# SCH_Aether_Zero_R0_2.net
KiCad netlist of a schematic drawn in EasyEDA
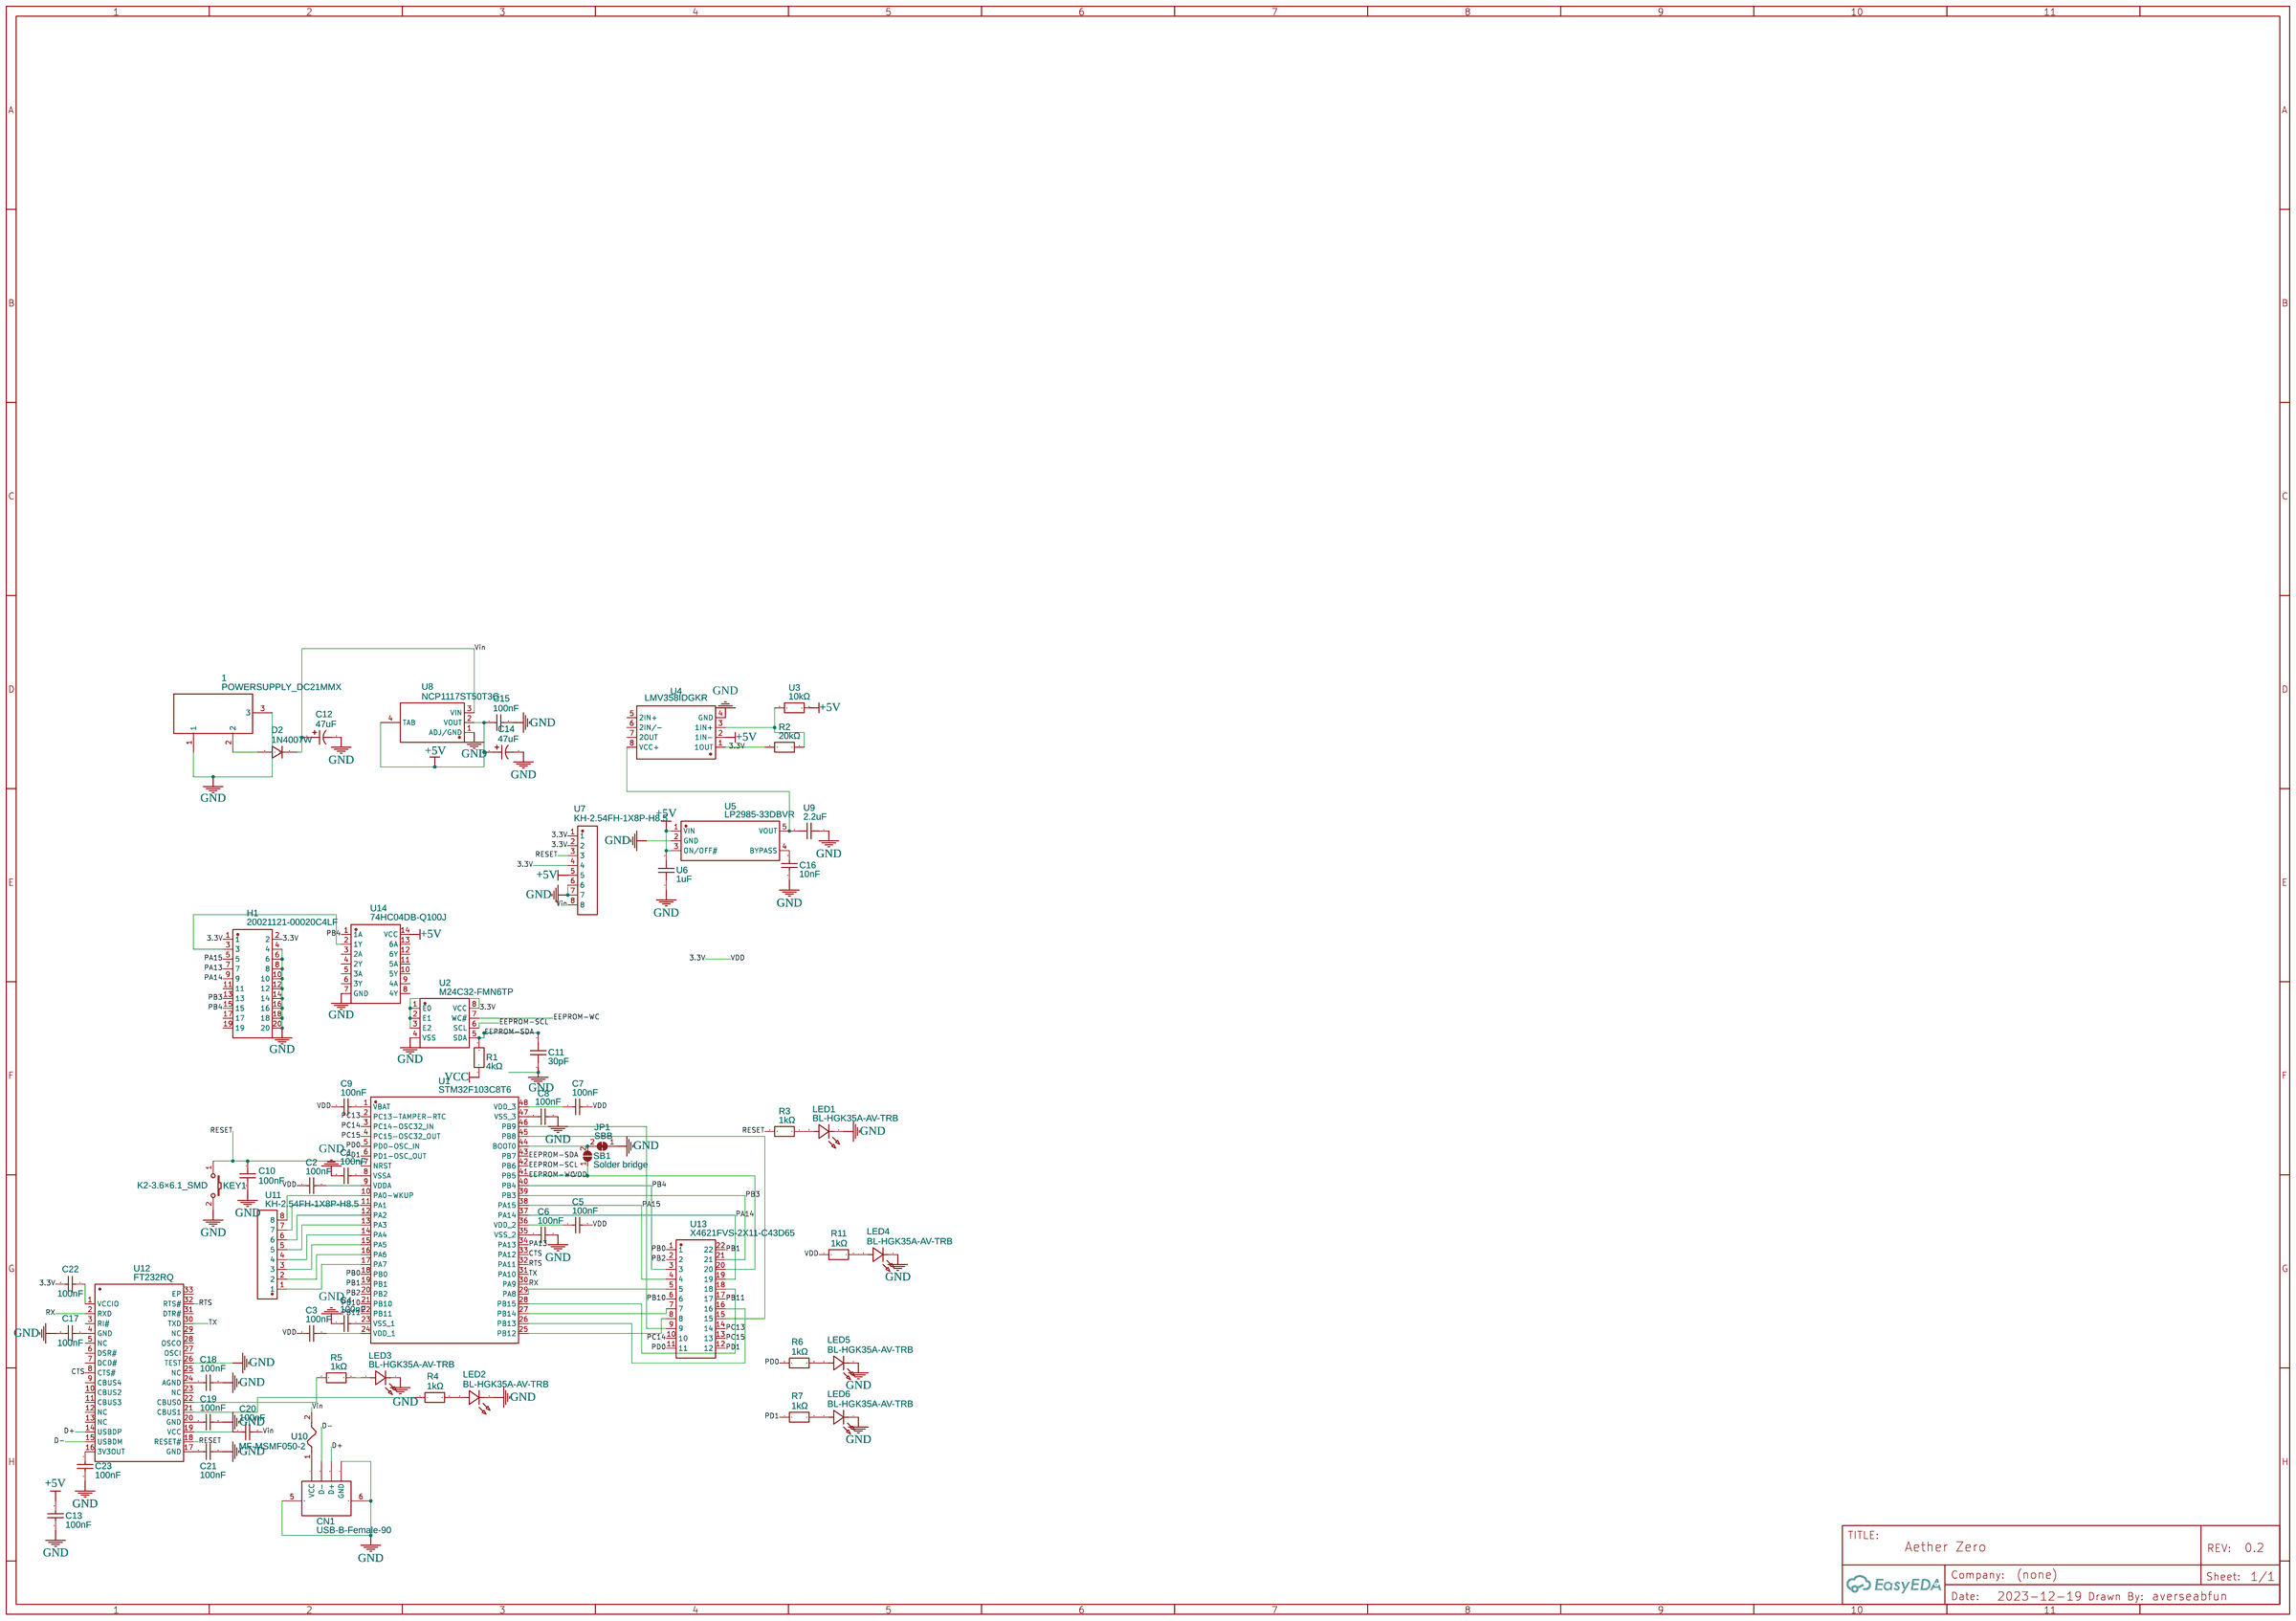
[diagram p0: schematic sheet]

(export (version "E")
  (design (tool "Eeschema 10.0.6"))
  (components
    (comp (ref "1") (value "POWERSUPPLY_DC21MMX") (libsource (lib "") (part "POWERSUPPLY_DC21MMX")))
    (comp (ref "C1")
      (value "100nF")
      (fields (field (name "Manufacturer Part") "0402B104K160NT") (field (name "Manufacturer") "FH(风华)"))
      (libsource (lib "") (part "0402B104K160NT"))
    )
    (comp (ref "C2")
      (value "100nF")
      (fields (field (name "Manufacturer Part") "0402B104K160NT") (field (name "Manufacturer") "FH(风华)"))
      (libsource (lib "") (part "0402B104K160NT"))
    )
    (comp (ref "C3")
      (value "100nF")
      (fields (field (name "Manufacturer Part") "0402B104K160NT") (field (name "Manufacturer") "FH(风华)"))
      (libsource (lib "") (part "0402B104K160NT"))
    )
    (comp (ref "C4")
      (value "100nF")
      (fields (field (name "Manufacturer Part") "0402B104K160NT") (field (name "Manufacturer") "FH(风华)"))
      (libsource (lib "") (part "0402B104K160NT"))
    )
    (comp (ref "C5")
      (value "100nF")
      (fields (field (name "Manufacturer Part") "0402B104K160NT") (field (name "Manufacturer") "FH(风华)"))
      (libsource (lib "") (part "0402B104K160NT_2"))
    )
    (comp (ref "C6")
      (value "100nF")
      (fields (field (name "Manufacturer Part") "0402B104K160NT") (field (name "Manufacturer") "FH(风华)"))
      (libsource (lib "") (part "0402B104K160NT_2"))
    )
    (comp (ref "C7")
      (value "100nF")
      (fields (field (name "Manufacturer Part") "0402B104K160NT") (field (name "Manufacturer") "FH(风华)"))
      (libsource (lib "") (part "0402B104K160NT_2"))
    )
    (comp (ref "C8")
      (value "100nF")
      (fields (field (name "Manufacturer Part") "0402B104K160NT") (field (name "Manufacturer") "FH(风华)"))
      (libsource (lib "") (part "0402B104K160NT_2"))
    )
    (comp (ref "C9")
      (value "100nF")
      (fields (field (name "Manufacturer Part") "0402B104K160NT") (field (name "Manufacturer") "FH(风华)"))
      (libsource (lib "") (part "0402B104K160NT"))
    )
    (comp (ref "C10")
      (value "100nF")
      (fields (field (name "Manufacturer Part") "0402B104K160NT") (field (name "Manufacturer") "FH(风华)"))
      (libsource (lib "") (part "0402B104K160NT_1"))
    )
    (comp (ref "C11")
      (value "30pF")
      (fields
        (field (name "Manufacturer Part") "AC0402JRNPO9BN300")
        (field (name "Manufacturer") "YAGEO(国巨)")
      )
      (libsource (lib "") (part "AC0402JRNPO9BN300"))
    )
    (comp (ref "C12")
      (value "47uF")
      (fields
        (field (name "Manufacturer Part") "RVT47UF35V67RV0039")
        (field (name "Manufacturer") "KNSCHA(科尼盛)")
      )
      (libsource (lib "") (part "RVT47UF35V67RV0039"))
    )
    (comp (ref "C13")
      (value "100nF")
      (fields (field (name "Manufacturer Part") "0402B104K160NT") (field (name "Manufacturer") "FH(风华)"))
      (libsource (lib "") (part "0402B104K160NT_3"))
    )
    (comp (ref "C14")
      (value "47uF")
      (fields
        (field (name "Manufacturer Part") "RVT47UF35V67RV0039")
        (field (name "Manufacturer") "KNSCHA(科尼盛)")
      )
      (libsource (lib "") (part "RVT47UF35V67RV0039"))
    )
    (comp (ref "C15")
      (value "100nF")
      (fields (field (name "Manufacturer Part") "0402B104K160NT") (field (name "Manufacturer") "FH(风华)"))
      (libsource (lib "") (part "0402B104K160NT_2"))
    )
    (comp (ref "C16")
      (value "10nF")
      (fields (field (name "Manufacturer Part") "0402B103K500NT") (field (name "Manufacturer") "FH(风华)"))
      (libsource (lib "") (part "0402B103K500NT"))
    )
    (comp (ref "C17")
      (value "100nF")
      (fields (field (name "Manufacturer Part") "0402B104K160NT") (field (name "Manufacturer") "FH(风华)"))
      (libsource (lib "") (part "0402B104K160NT"))
    )
    (comp (ref "C18")
      (value "100nF")
      (fields (field (name "Manufacturer Part") "0402B104K160NT") (field (name "Manufacturer") "FH(风华)"))
      (libsource (lib "") (part "0402B104K160NT_2"))
    )
    (comp (ref "C19")
      (value "100nF")
      (fields (field (name "Manufacturer Part") "0402B104K160NT") (field (name "Manufacturer") "FH(风华)"))
      (libsource (lib "") (part "0402B104K160NT_2"))
    )
    (comp (ref "C20")
      (value "100nF")
      (fields (field (name "Manufacturer Part") "0402B104K160NT") (field (name "Manufacturer") "FH(风华)"))
      (libsource (lib "") (part "0402B104K160NT_2"))
    )
    (comp (ref "C21")
      (value "100nF")
      (fields (field (name "Manufacturer Part") "0402B104K160NT") (field (name "Manufacturer") "FH(风华)"))
      (libsource (lib "") (part "0402B104K160NT_2"))
    )
    (comp (ref "C22")
      (value "100nF")
      (fields (field (name "Manufacturer Part") "0402B104K160NT") (field (name "Manufacturer") "FH(风华)"))
      (libsource (lib "") (part "0402B104K160NT"))
    )
    (comp (ref "C23")
      (value "100nF")
      (fields (field (name "Manufacturer Part") "0402B104K160NT") (field (name "Manufacturer") "FH(风华)"))
      (libsource (lib "") (part "0402B104K160NT_1"))
    )
    (comp (ref "CN1")
      (value "USB-B-Female-90")
      (fields (field (name "Manufacturer Part") "921-111A1010D10200") (field (name "Manufacturer") "精拓金"))
      (libsource (lib "") (part "USB-B-Female-90"))
    )
    (comp (ref "D2")
      (value "1N4007W")
      (fields (field (name "Manufacturer") "BLUE ROCKET"))
      (libsource (lib "") (part "1N4007W"))
    )
    (comp (ref "H1")
      (value "20021121-00020C4LF")
      (fields (field (name "Manufacturer") "Amphenol"))
      (libsource (lib "") (part "20021121-00020C4LF"))
    )
    (comp (ref "JP1") (value "SBB") (libsource (lib "") (part "SBB")))
    (comp (ref "KEY1")
      (value "K2-3.6×6.1_SMD")
      (fields (field (name "Manufacturer Part") "K2-1107ST-A4SW-06"))
      (libsource (lib "") (part "K2-3.6×6.1_SMD"))
    )
    (comp (ref "LED1")
      (value "BL-HGK35A-AV-TRB")
      (fields (field (name "Manufacturer") "BrtLed(佰鸿)"))
      (libsource (lib "") (part "BL-HGK35A-AV-TRB"))
    )
    (comp (ref "LED2")
      (value "BL-HGK35A-AV-TRB")
      (fields (field (name "Manufacturer") "BrtLed(佰鸿)"))
      (libsource (lib "") (part "BL-HGK35A-AV-TRB"))
    )
    (comp (ref "LED3")
      (value "BL-HGK35A-AV-TRB")
      (fields (field (name "Manufacturer") "BrtLed(佰鸿)"))
      (libsource (lib "") (part "BL-HGK35A-AV-TRB"))
    )
    (comp (ref "LED4")
      (value "BL-HGK35A-AV-TRB")
      (fields (field (name "Manufacturer") "BrtLed(佰鸿)"))
      (libsource (lib "") (part "BL-HGK35A-AV-TRB"))
    )
    (comp (ref "LED5")
      (value "BL-HGK35A-AV-TRB")
      (fields (field (name "Manufacturer") "BrtLed(佰鸿)"))
      (libsource (lib "") (part "BL-HGK35A-AV-TRB"))
    )
    (comp (ref "LED6")
      (value "BL-HGK35A-AV-TRB")
      (fields (field (name "Manufacturer") "BrtLed(佰鸿)"))
      (libsource (lib "") (part "BL-HGK35A-AV-TRB"))
    )
    (comp (ref "R1")
      (value "4kΩ")
      (fields (field (name "Manufacturer Part") "RN732BTTD4001B25") (field (name "Manufacturer") "KOA"))
      (libsource (lib "") (part "RN732BTTD4001B25"))
    )
    (comp (ref "R2")
      (value "20kΩ")
      (fields (field (name "Manufacturer Part") "RT0402BRD0720KL") (field (name "Manufacturer") "YAGEO(国巨)"))
      (libsource (lib "") (part "RT0402BRD0720KL"))
    )
    (comp (ref "R3")
      (value "1kΩ")
      (fields (field (name "Manufacturer Part") "CR-03JA7----1K") (field (name "Manufacturer") "Viking Tech"))
      (libsource (lib "") (part "CR-03JA7----1K"))
    )
    (comp (ref "R4")
      (value "1kΩ")
      (fields (field (name "Manufacturer Part") "CR-03JA7----1K") (field (name "Manufacturer") "Viking Tech"))
      (libsource (lib "") (part "CR-03JA7----1K_1"))
    )
    (comp (ref "R5")
      (value "1kΩ")
      (fields (field (name "Manufacturer Part") "CR-03JA7----1K") (field (name "Manufacturer") "Viking Tech"))
      (libsource (lib "") (part "CR-03JA7----1K"))
    )
    (comp (ref "R6")
      (value "1kΩ")
      (fields (field (name "Manufacturer Part") "CR-03JA7----1K") (field (name "Manufacturer") "Viking Tech"))
      (libsource (lib "") (part "CR-03JA7----1K_1"))
    )
    (comp (ref "R7")
      (value "1kΩ")
      (fields (field (name "Manufacturer Part") "CR-03JA7----1K") (field (name "Manufacturer") "Viking Tech"))
      (libsource (lib "") (part "CR-03JA7----1K_1"))
    )
    (comp (ref "R11")
      (value "1kΩ")
      (fields (field (name "Manufacturer Part") "CR-03JA7----1K") (field (name "Manufacturer") "Viking Tech"))
      (libsource (lib "") (part "CR-03JA7----1K_1"))
    )
    (comp (ref "SB1")
      (value "Solder bridge")
      (fields (field (name "Manufacturer Part") "DNP"))
      (libsource (lib "") (part "Solder bridge"))
    )
    (comp (ref "U1")
      (value "STM32F103C8T6")
      (fields (field (name "Manufacturer") "ST(意法半导体)"))
      (libsource (lib "") (part "STM32F103C8T6"))
    )
    (comp (ref "U2")
      (value "M24C32-FMN6TP")
      (fields (field (name "Manufacturer") "ST(意法半导体)"))
      (libsource (lib "") (part "M24C32-FMN6TP"))
    )
    (comp (ref "U3")
      (value "10kΩ")
      (fields
        (field (name "Manufacturer Part") "TC0625B1002T5J")
        (field (name "Manufacturer") "UNI-ROYAL(厚声)")
      )
      (libsource (lib "") (part "TC0625B1002T5J"))
    )
    (comp (ref "U4")
      (value "LMV358IDGKR")
      (fields (field (name "Manufacturer") "TI(德州仪器)"))
      (libsource (lib "") (part "LMV358IDGKR"))
    )
    (comp (ref "U5")
      (value "LP2985-33DBVR")
      (fields (field (name "Manufacturer") "TI(德州仪器)"))
      (libsource (lib "") (part "LP2985-33DBVR"))
    )
    (comp (ref "U6")
      (value "1uF")
      (fields (field (name "Manufacturer Part") "CGA5L3X8R1H105KT0Y0N") (field (name "Manufacturer") "TDK"))
      (libsource (lib "") (part "CGA5L3X8R1H105KT0Y0N"))
    )
    (comp (ref "U7")
      (value "KH-2.54FH-1X8P-H8.5")
      (fields (field (name "Manufacturer") "kinghelm(金航标)"))
      (libsource (lib "") (part "KH-2.54FH-1X8P-H8.5_1"))
    )
    (comp (ref "U8")
      (value "NCP1117ST50T3G")
      (fields (field (name "Manufacturer") "onsemi(安森美)"))
      (libsource (lib "") (part "NCP1117ST50T3G"))
    )
    (comp (ref "U9")
      (value "2.2uF")
      (fields (field (name "Manufacturer Part") "0805X225K250CT") (field (name "Manufacturer") "Walsin(华新科)"))
      (libsource (lib "") (part "0805X225K250CT_C5122273"))
    )
    (comp (ref "U10")
      (value "MF-MSMF050-2")
      (fields (field (name "Manufacturer") "BOURNS"))
      (libsource (lib "") (part "MF-MSMF050-2"))
    )
    (comp (ref "U11")
      (value "KH-2.54FH-1X8P-H8.5")
      (fields (field (name "Manufacturer") "kinghelm(金航标)"))
      (libsource (lib "") (part "KH-2.54FH-1X8P-H8.5"))
    )
    (comp (ref "U12")
      (value "FT232RQ")
      (fields (field (name "Manufacturer Part") "FT232RQ-REEL") (field (name "Manufacturer") "FTDI(飞特帝亚)"))
      (libsource (lib "") (part "FT232RQ"))
    )
    (comp (ref "U13")
      (value "X4621FVS-2X11-C43D65")
      (fields
        (field (name "Manufacturer Part") "X4621FVS-2x11-C43D65")
        (field (name "Manufacturer") "XKB Connectivity(中国星坤)")
      )
      (libsource (lib "") (part "X4621FVS-2X11-C43D65"))
    )
    (comp (ref "U14")
      (value "74HC04DB-Q100J")
      (fields (field (name "Manufacturer") "Nexperia(安世)"))
      (libsource (lib "") (part "74HC04DB-Q100J"))
    )
  )
  (nets
    (net (code "1") (name "+5V") (class "Default")
      (node (ref "C13") (pin "2") (pinfunction "2_2") (pintype "input"))
      (node (ref "C14") (pin "1") (pinfunction "1_1") (pintype "input"))
      (node (ref "C15") (pin "1") (pinfunction "1_1") (pintype "input"))
      (node (ref "U14") (pin "14") (pinfunction "VCC_14") (pintype "unspecified"))
      (node (ref "U3") (pin "2") (pinfunction "2_2") (pintype "unspecified"))
      (node (ref "U4") (pin "2") (pinfunction "1IN-_2") (pintype "unspecified"))
      (node (ref "U5") (pin "1") (pinfunction "VIN_1") (pintype "unspecified"))
      (node (ref "U5") (pin "3") (pinfunction "ON/OFF#_3") (pintype "unspecified"))
      (node (ref "U6") (pin "2") (pinfunction "2_2") (pintype "unspecified"))
      (node (ref "U7") (pin "5") (pinfunction "5_5") (pintype "unspecified"))
      (node (ref "U8") (pin "2") (pinfunction "VOUT_2") (pintype "unspecified"))
      (node (ref "U8") (pin "4") (pinfunction "TAB_4") (pintype "unspecified"))
    )
    (net (code "2") (name "/3.3V") (class "Default")
      (node (ref "C2") (pin "2") (pinfunction "2_2") (pintype "input"))
      (node (ref "C22") (pin "2") (pinfunction "2_2") (pintype "input"))
      (node (ref "C3") (pin "2") (pinfunction "2_2") (pintype "input"))
      (node (ref "C5") (pin "2") (pinfunction "2_2") (pintype "input"))
      (node (ref "C7") (pin "2") (pinfunction "2_2") (pintype "input"))
      (node (ref "C9") (pin "2") (pinfunction "2_2") (pintype "input"))
      (node (ref "H1") (pin "1") (pinfunction "1_1") (pintype "unspecified"))
      (node (ref "H1") (pin "2") (pinfunction "2_2") (pintype "unspecified"))
      (node (ref "R11") (pin "1") (pinfunction "1_1") (pintype "unspecified"))
      (node (ref "R2") (pin "1") (pinfunction "1_1") (pintype "unspecified"))
      (node (ref "SB1") (pin "1") (pinfunction "A_1") (pintype "unspecified"))
      (node (ref "U1") (pin "41") (pinfunction "PB5_41") (pintype "unspecified"))
      (node (ref "U13") (pin "20") (pinfunction "20_20") (pintype "unspecified"))
      (node (ref "U2") (pin "1") (pinfunction "E0_1") (pintype "unspecified"))
      (node (ref "U2") (pin "2") (pinfunction "E1_2") (pintype "unspecified"))
      (node (ref "U2") (pin "3") (pinfunction "E2_3") (pintype "unspecified"))
      (node (ref "U2") (pin "7") (pinfunction "WC#_7") (pintype "unspecified"))
      (node (ref "U2") (pin "8") (pinfunction "VCC_8") (pintype "unspecified"))
      (node (ref "U4") (pin "1") (pinfunction "1OUT_1") (pintype "unspecified"))
      (node (ref "U7") (pin "1") (pinfunction "1_1") (pintype "unspecified"))
      (node (ref "U7") (pin "2") (pinfunction "2_2") (pintype "unspecified"))
      (node (ref "U7") (pin "4") (pinfunction "4_4") (pintype "unspecified"))
    )
    (net (code "3") (name "/CTS") (class "Default")
      (node (ref "U1") (pin "33") (pinfunction "PA12_33") (pintype "unspecified"))
      (node (ref "U12") (pin "8") (pinfunction "CTS#_8") (pintype "unspecified"))
    )
    (net (code "4") (name "/D+") (class "Default")
      (node (ref "CN1") (pin "3") (pinfunction "D+_3") (pintype "input"))
      (node (ref "U12") (pin "14") (pinfunction "USBDP_14") (pintype "unspecified"))
    )
    (net (code "5") (name "/D-") (class "Default")
      (node (ref "CN1") (pin "2") (pinfunction "D-_2") (pintype "input"))
      (node (ref "U12") (pin "15") (pinfunction "USBDM_15") (pintype "unspecified"))
    )
    (net (code "6") (name "/EEPROM-SCL") (class "Default")
      (node (ref "U1") (pin "42") (pinfunction "PB6_42") (pintype "unspecified"))
      (node (ref "U2") (pin "6") (pinfunction "SCL_6") (pintype "unspecified"))
    )
    (net (code "7") (name "/EEPROM-SDA") (class "Default")
      (node (ref "C11") (pin "1") (pinfunction "1_1") (pintype "unspecified"))
      (node (ref "R1") (pin "2") (pinfunction "2_2") (pintype "unspecified"))
      (node (ref "U1") (pin "43") (pinfunction "PB7_43") (pintype "unspecified"))
      (node (ref "U2") (pin "5") (pinfunction "SDA_5") (pintype "unspecified"))
    )
    (net (code "8") (name "/PA13") (class "Default")
      (node (ref "H1") (pin "7") (pinfunction "7_7") (pintype "unspecified"))
      (node (ref "U1") (pin "34") (pinfunction "PA13_34") (pintype "unspecified"))
    )
    (net (code "9") (name "/PA14") (class "Default")
      (node (ref "H1") (pin "9") (pinfunction "9_9") (pintype "unspecified"))
      (node (ref "U1") (pin "37") (pinfunction "PA14_37") (pintype "unspecified"))
      (node (ref "U13") (pin "19") (pinfunction "19_19") (pintype "unspecified"))
    )
    (net (code "10") (name "/PA15") (class "Default")
      (node (ref "H1") (pin "5") (pinfunction "5_5") (pintype "unspecified"))
      (node (ref "U1") (pin "38") (pinfunction "PA15_38") (pintype "unspecified"))
      (node (ref "U13") (pin "4") (pinfunction "4_4") (pintype "unspecified"))
    )
    (net (code "11") (name "/PB0") (class "Default")
      (node (ref "U1") (pin "18") (pinfunction "PB0_18") (pintype "unspecified"))
      (node (ref "U13") (pin "1") (pinfunction "1_1") (pintype "unspecified"))
    )
    (net (code "12") (name "/PB1") (class "Default")
      (node (ref "U1") (pin "19") (pinfunction "PB1_19") (pintype "unspecified"))
      (node (ref "U13") (pin "22") (pinfunction "22_22") (pintype "unspecified"))
    )
    (net (code "13") (name "/PB2") (class "Default")
      (node (ref "U1") (pin "20") (pinfunction "PB2_20") (pintype "unspecified"))
      (node (ref "U13") (pin "2") (pinfunction "2_2") (pintype "unspecified"))
    )
    (net (code "14") (name "/PB3") (class "Default")
      (node (ref "H1") (pin "13") (pinfunction "13_13") (pintype "unspecified"))
      (node (ref "U1") (pin "39") (pinfunction "PB3_39") (pintype "unspecified"))
      (node (ref "U13") (pin "21") (pinfunction "21_21") (pintype "unspecified"))
    )
    (net (code "15") (name "/PB4") (class "Default")
      (node (ref "H1") (pin "15") (pinfunction "15_15") (pintype "unspecified"))
      (node (ref "U1") (pin "40") (pinfunction "PB4_40") (pintype "unspecified"))
      (node (ref "U13") (pin "3") (pinfunction "3_3") (pintype "unspecified"))
      (node (ref "U14") (pin "1") (pinfunction "1A_1") (pintype "unspecified"))
    )
    (net (code "16") (name "/PB10") (class "Default")
      (node (ref "U1") (pin "21") (pinfunction "PB10_21") (pintype "unspecified"))
      (node (ref "U13") (pin "6") (pinfunction "6_6") (pintype "unspecified"))
    )
    (net (code "17") (name "/PB11") (class "Default")
      (node (ref "U1") (pin "22") (pinfunction "PB11_22") (pintype "unspecified"))
      (node (ref "U13") (pin "17") (pinfunction "17_17") (pintype "unspecified"))
    )
    (net (code "18") (name "/PC13") (class "Default")
      (node (ref "U1") (pin "2") (pinfunction "PC13-TAMPER-RTC_2") (pintype "unspecified"))
      (node (ref "U13") (pin "14") (pinfunction "14_14") (pintype "unspecified"))
    )
    (net (code "19") (name "/PC14") (class "Default")
      (node (ref "U1") (pin "3") (pinfunction "PC14-OSC32_IN_3") (pintype "unspecified"))
      (node (ref "U13") (pin "10") (pinfunction "10_10") (pintype "unspecified"))
    )
    (net (code "20") (name "/PC15") (class "Default")
      (node (ref "U1") (pin "4") (pinfunction "PC15-OSC32_OUT_4") (pintype "unspecified"))
      (node (ref "U13") (pin "13") (pinfunction "13_13") (pintype "unspecified"))
    )
    (net (code "21") (name "/PD0") (class "Default")
      (node (ref "R6") (pin "1") (pinfunction "1_1") (pintype "unspecified"))
      (node (ref "U1") (pin "5") (pinfunction "PD0-OSC_IN_5") (pintype "unspecified"))
      (node (ref "U13") (pin "11") (pinfunction "11_11") (pintype "unspecified"))
    )
    (net (code "22") (name "/PD1") (class "Default")
      (node (ref "R7") (pin "1") (pinfunction "1_1") (pintype "unspecified"))
      (node (ref "U1") (pin "6") (pinfunction "PD1-OSC_OUT_6") (pintype "unspecified"))
      (node (ref "U13") (pin "12") (pinfunction "12_12") (pintype "unspecified"))
    )
    (net (code "23") (name "/RESET") (class "Default")
      (node (ref "C10") (pin "1") (pinfunction "1_1") (pintype "input"))
      (node (ref "KEY1") (pin "1") (pinfunction "1_1") (pintype "unspecified"))
      (node (ref "R3") (pin "2") (pinfunction "2_2") (pintype "unspecified"))
      (node (ref "U1") (pin "7") (pinfunction "NRST_7") (pintype "unspecified"))
      (node (ref "U12") (pin "18") (pinfunction "RESET#_18") (pintype "unspecified"))
      (node (ref "U7") (pin "3") (pinfunction "3_3") (pintype "unspecified"))
    )
    (net (code "24") (name "/RTS") (class "Default")
      (node (ref "U1") (pin "32") (pinfunction "PA11_32") (pintype "unspecified"))
      (node (ref "U12") (pin "32") (pinfunction "RTS#_32") (pintype "unspecified"))
    )
    (net (code "25") (name "/RX") (class "Default")
      (node (ref "U1") (pin "30") (pinfunction "PA9_30") (pintype "unspecified"))
      (node (ref "U12") (pin "2") (pinfunction "RXD_2") (pintype "unspecified"))
    )
    (net (code "26") (name "/TX") (class "Default")
      (node (ref "U1") (pin "31") (pinfunction "PA10_31") (pintype "unspecified"))
      (node (ref "U12") (pin "30") (pinfunction "TXD_30") (pintype "unspecified"))
    )
    (net (code "27") (name "/Vin") (class "Default")
      (node (ref "C12") (pin "1") (pinfunction "1_1") (pintype "input"))
      (node (ref "C20") (pin "2") (pinfunction "2_2") (pintype "input"))
      (node (ref "D2") (pin "1") (pinfunction "1_1") (pintype "unspecified"))
      (node (ref "U10") (pin "2") (pinfunction "2_2") (pintype "unspecified"))
      (node (ref "U7") (pin "8") (pinfunction "8_8") (pintype "unspecified"))
      (node (ref "U8") (pin "3") (pinfunction "VIN_3") (pintype "unspecified"))
    )
    (net (code "28") (name "GND") (class "Default")
      (node (ref "1") (pin "1") (pinfunction "1_1") (pintype "bidirectional"))
      (node (ref "1") (pin "3") (pinfunction "3_3") (pintype "bidirectional"))
      (node (ref "C1") (pin "2") (pinfunction "2_2") (pintype "input"))
      (node (ref "C10") (pin "2") (pinfunction "2_2") (pintype "input"))
      (node (ref "C11") (pin "2") (pinfunction "2_2") (pintype "unspecified"))
      (node (ref "C12") (pin "2") (pinfunction "2_2") (pintype "input"))
      (node (ref "C13") (pin "1") (pinfunction "1_1") (pintype "input"))
      (node (ref "C14") (pin "2") (pinfunction "2_2") (pintype "input"))
      (node (ref "C15") (pin "2") (pinfunction "2_2") (pintype "input"))
      (node (ref "C16") (pin "1") (pinfunction "1_1") (pintype "input"))
      (node (ref "C17") (pin "2") (pinfunction "2_2") (pintype "input"))
      (node (ref "C18") (pin "2") (pinfunction "2_2") (pintype "input"))
      (node (ref "C19") (pin "2") (pinfunction "2_2") (pintype "input"))
      (node (ref "C21") (pin "2") (pinfunction "2_2") (pintype "input"))
      (node (ref "C23") (pin "2") (pinfunction "2_2") (pintype "input"))
      (node (ref "C4") (pin "2") (pinfunction "2_2") (pintype "input"))
      (node (ref "C6") (pin "2") (pinfunction "2_2") (pintype "input"))
      (node (ref "C8") (pin "2") (pinfunction "2_2") (pintype "input"))
      (node (ref "CN1") (pin "4") (pinfunction "GND_4") (pintype "input"))
      (node (ref "CN1") (pin "5") (pinfunction "SH1_5") (pintype "unspecified"))
      (node (ref "CN1") (pin "6") (pinfunction "SH2_6") (pintype "unspecified"))
      (node (ref "H1") (pin "10") (pinfunction "10_10") (pintype "unspecified"))
      (node (ref "H1") (pin "12") (pinfunction "12_12") (pintype "unspecified"))
      (node (ref "H1") (pin "14") (pinfunction "14_14") (pintype "unspecified"))
      (node (ref "H1") (pin "16") (pinfunction "16_16") (pintype "unspecified"))
      (node (ref "H1") (pin "18") (pinfunction "18_18") (pintype "unspecified"))
      (node (ref "H1") (pin "20") (pinfunction "20_20") (pintype "unspecified"))
      (node (ref "H1") (pin "4") (pinfunction "4_4") (pintype "unspecified"))
      (node (ref "H1") (pin "6") (pinfunction "6_6") (pintype "unspecified"))
      (node (ref "H1") (pin "8") (pinfunction "8_8") (pintype "unspecified"))
      (node (ref "JP1") (pin "1") (pinfunction "A_1") (pintype "unspecified"))
      (node (ref "KEY1") (pin "2") (pinfunction "2_2") (pintype "unspecified"))
      (node (ref "LED1") (pin "1") (pinfunction "K_1") (pintype "unspecified"))
      (node (ref "LED2") (pin "1") (pinfunction "K_1") (pintype "unspecified"))
      (node (ref "LED3") (pin "1") (pinfunction "K_1") (pintype "unspecified"))
      (node (ref "LED4") (pin "1") (pinfunction "K_1") (pintype "unspecified"))
      (node (ref "LED5") (pin "1") (pinfunction "K_1") (pintype "unspecified"))
      (node (ref "LED6") (pin "1") (pinfunction "K_1") (pintype "unspecified"))
      (node (ref "U12") (pin "26") (pinfunction "TEST_26") (pintype "unspecified"))
      (node (ref "U14") (pin "7") (pinfunction "GND_7") (pintype "unspecified"))
      (node (ref "U2") (pin "4") (pinfunction "VSS_4") (pintype "unspecified"))
      (node (ref "U4") (pin "4") (pinfunction "GND_4") (pintype "unspecified"))
      (node (ref "U5") (pin "2") (pinfunction "GND_2") (pintype "unspecified"))
      (node (ref "U6") (pin "1") (pinfunction "1_1") (pintype "unspecified"))
      (node (ref "U7") (pin "6") (pinfunction "6_6") (pintype "unspecified"))
      (node (ref "U7") (pin "7") (pinfunction "7_7") (pintype "unspecified"))
      (node (ref "U8") (pin "1") (pinfunction "ADJ/GND_1") (pintype "unspecified"))
      (node (ref "U9") (pin "1") (pinfunction "1_1") (pintype "unspecified"))
    )
    (net (code "29") (name "Net-(1-Pad2)") (class "Default")
      (node (ref "1") (pin "2") (pinfunction "2_2") (pintype "bidirectional"))
      (node (ref "D2") (pin "2") (pinfunction "2_2") (pintype "unspecified"))
    )
    (net (code "30") (name "Net-(C17-Pad1)") (class "Default")
      (node (ref "C17") (pin "1") (pinfunction "1_1") (pintype "input"))
      (node (ref "U12") (pin "4") (pinfunction "GND_4") (pintype "unspecified"))
    )
    (net (code "31") (name "Net-(C19-Pad1)") (class "Default")
      (node (ref "C19") (pin "1") (pinfunction "1_1") (pintype "input"))
      (node (ref "U12") (pin "20") (pinfunction "GND_20") (pintype "unspecified"))
    )
    (net (code "32") (name "Net-(C21-Pad1)") (class "Default")
      (node (ref "C21") (pin "1") (pinfunction "1_1") (pintype "input"))
      (node (ref "U12") (pin "17") (pinfunction "GND_17") (pintype "unspecified"))
    )
    (net (code "33") (name "Net-(CN1-VCC)") (class "Default")
      (node (ref "CN1") (pin "1") (pinfunction "VCC_1") (pintype "input"))
      (node (ref "U10") (pin "1") (pinfunction "1_1") (pintype "unspecified"))
    )
    (net (code "34") (name "Net-(JP1-B)") (class "Default")
      (node (ref "JP1") (pin "2") (pinfunction "B_2") (pintype "unspecified"))
      (node (ref "SB1") (pin "2") (pinfunction "B_2") (pintype "unspecified"))
      (node (ref "U1") (pin "44") (pinfunction "BOOT0_44") (pintype "unspecified"))
    )
    (net (code "35") (name "Net-(LED1-A)") (class "Default")
      (node (ref "LED1") (pin "2") (pinfunction "A_2") (pintype "unspecified"))
      (node (ref "R3") (pin "1") (pinfunction "1_1") (pintype "unspecified"))
    )
    (net (code "36") (name "Net-(LED2-A)") (class "Default")
      (node (ref "LED2") (pin "2") (pinfunction "A_2") (pintype "unspecified"))
      (node (ref "R4") (pin "2") (pinfunction "2_2") (pintype "unspecified"))
    )
    (net (code "37") (name "Net-(LED3-A)") (class "Default")
      (node (ref "LED3") (pin "2") (pinfunction "A_2") (pintype "unspecified"))
      (node (ref "R5") (pin "1") (pinfunction "1_1") (pintype "unspecified"))
    )
    (net (code "38") (name "Net-(LED4-A)") (class "Default")
      (node (ref "LED4") (pin "2") (pinfunction "A_2") (pintype "unspecified"))
      (node (ref "R11") (pin "2") (pinfunction "2_2") (pintype "unspecified"))
    )
    (net (code "39") (name "Net-(LED5-A)") (class "Default")
      (node (ref "LED5") (pin "2") (pinfunction "A_2") (pintype "unspecified"))
      (node (ref "R6") (pin "2") (pinfunction "2_2") (pintype "unspecified"))
    )
    (net (code "40") (name "Net-(LED6-A)") (class "Default")
      (node (ref "LED6") (pin "2") (pinfunction "A_2") (pintype "unspecified"))
      (node (ref "R7") (pin "2") (pinfunction "2_2") (pintype "unspecified"))
    )
    (net (code "41") (name "Net-(U1-PA0-WKUP)") (class "Default")
      (node (ref "U1") (pin "10") (pinfunction "PA0-WKUP_10") (pintype "unspecified"))
      (node (ref "U11") (pin "8") (pinfunction "8_8") (pintype "unspecified"))
    )
    (net (code "42") (name "Net-(U1-PA1)") (class "Default")
      (node (ref "U1") (pin "11") (pinfunction "PA1_11") (pintype "unspecified"))
      (node (ref "U11") (pin "7") (pinfunction "7_7") (pintype "unspecified"))
    )
    (net (code "43") (name "Net-(U1-PA2)") (class "Default")
      (node (ref "U1") (pin "12") (pinfunction "PA2_12") (pintype "unspecified"))
      (node (ref "U11") (pin "6") (pinfunction "6_6") (pintype "unspecified"))
    )
    (net (code "44") (name "Net-(U1-PA3)") (class "Default")
      (node (ref "U1") (pin "13") (pinfunction "PA3_13") (pintype "unspecified"))
      (node (ref "U11") (pin "5") (pinfunction "5_5") (pintype "unspecified"))
    )
    (net (code "45") (name "Net-(U1-PA4)") (class "Default")
      (node (ref "U1") (pin "14") (pinfunction "PA4_14") (pintype "unspecified"))
      (node (ref "U11") (pin "4") (pinfunction "4_4") (pintype "unspecified"))
    )
    (net (code "46") (name "Net-(U1-PA5)") (class "Default")
      (node (ref "U1") (pin "15") (pinfunction "PA5_15") (pintype "unspecified"))
      (node (ref "U11") (pin "3") (pinfunction "3_3") (pintype "unspecified"))
    )
    (net (code "47") (name "Net-(U1-PA6)") (class "Default")
      (node (ref "U1") (pin "16") (pinfunction "PA6_16") (pintype "unspecified"))
      (node (ref "U11") (pin "2") (pinfunction "2_2") (pintype "unspecified"))
    )
    (net (code "48") (name "Net-(U1-PA7)") (class "Default")
      (node (ref "U1") (pin "17") (pinfunction "PA7_17") (pintype "unspecified"))
      (node (ref "U11") (pin "1") (pinfunction "1_1") (pintype "unspecified"))
    )
    (net (code "49") (name "Net-(U1-PA8)") (class "Default")
      (node (ref "U1") (pin "29") (pinfunction "PA8_29") (pintype "unspecified"))
      (node (ref "U13") (pin "5") (pinfunction "5_5") (pintype "unspecified"))
    )
    (net (code "50") (name "Net-(U1-PB8)") (class "Default")
      (node (ref "U1") (pin "45") (pinfunction "PB8_45") (pintype "unspecified"))
      (node (ref "U13") (pin "15") (pinfunction "15_15") (pintype "unspecified"))
    )
    (net (code "51") (name "Net-(U1-PB9)") (class "Default")
      (node (ref "U1") (pin "46") (pinfunction "PB9_46") (pintype "unspecified"))
      (node (ref "U13") (pin "9") (pinfunction "9_9") (pintype "unspecified"))
    )
    (net (code "52") (name "Net-(U1-PB12)") (class "Default")
      (node (ref "U1") (pin "25") (pinfunction "PB12_25") (pintype "unspecified"))
      (node (ref "U13") (pin "8") (pinfunction "8_8") (pintype "unspecified"))
    )
    (net (code "53") (name "Net-(U1-PB13)") (class "Default")
      (node (ref "U1") (pin "26") (pinfunction "PB13_26") (pintype "unspecified"))
      (node (ref "U13") (pin "16") (pinfunction "16_16") (pintype "unspecified"))
    )
    (net (code "54") (name "Net-(U1-PB14)") (class "Default")
      (node (ref "U1") (pin "27") (pinfunction "PB14_27") (pintype "unspecified"))
      (node (ref "U13") (pin "7") (pinfunction "7_7") (pintype "unspecified"))
    )
    (net (code "55") (name "Net-(U1-PB15)") (class "Default")
      (node (ref "U1") (pin "28") (pinfunction "PB15_28") (pintype "unspecified"))
      (node (ref "U13") (pin "18") (pinfunction "18_18") (pintype "unspecified"))
    )
    (net (code "56") (name "Net-(U1-VBAT)") (class "Default")
      (node (ref "C9") (pin "1") (pinfunction "1_1") (pintype "input"))
      (node (ref "U1") (pin "1") (pinfunction "VBAT_1") (pintype "unspecified"))
    )
    (net (code "57") (name "Net-(U1-VDDA)") (class "Default")
      (node (ref "C2") (pin "1") (pinfunction "1_1") (pintype "input"))
      (node (ref "U1") (pin "9") (pinfunction "VDDA_9") (pintype "unspecified"))
    )
    (net (code "58") (name "Net-(U1-VDD_1)") (class "Default")
      (node (ref "C3") (pin "1") (pinfunction "1_1") (pintype "input"))
      (node (ref "U1") (pin "24") (pinfunction "VDD_1_24") (pintype "unspecified"))
    )
    (net (code "59") (name "Net-(U1-VDD_2)") (class "Default")
      (node (ref "C5") (pin "1") (pinfunction "1_1") (pintype "input"))
      (node (ref "U1") (pin "36") (pinfunction "VDD_2_36") (pintype "unspecified"))
    )
    (net (code "60") (name "Net-(U1-VDD_3)") (class "Default")
      (node (ref "C7") (pin "1") (pinfunction "1_1") (pintype "input"))
      (node (ref "U1") (pin "48") (pinfunction "VDD_3_48") (pintype "unspecified"))
    )
    (net (code "61") (name "Net-(U1-VSSA)") (class "Default")
      (node (ref "C1") (pin "1") (pinfunction "1_1") (pintype "input"))
      (node (ref "U1") (pin "8") (pinfunction "VSSA_8") (pintype "unspecified"))
    )
    (net (code "62") (name "Net-(U1-VSS_1)") (class "Default")
      (node (ref "C4") (pin "1") (pinfunction "1_1") (pintype "input"))
      (node (ref "U1") (pin "23") (pinfunction "VSS_1_23") (pintype "unspecified"))
    )
    (net (code "63") (name "Net-(U1-VSS_2)") (class "Default")
      (node (ref "C6") (pin "1") (pinfunction "1_1") (pintype "input"))
      (node (ref "U1") (pin "35") (pinfunction "VSS_2_35") (pintype "unspecified"))
    )
    (net (code "64") (name "Net-(U1-VSS_3)") (class "Default")
      (node (ref "C8") (pin "1") (pinfunction "1_1") (pintype "input"))
      (node (ref "U1") (pin "47") (pinfunction "VSS_3_47") (pintype "unspecified"))
    )
    (net (code "65") (name "Net-(U4-1IN+)") (class "Default")
      (node (ref "R2") (pin "2") (pinfunction "2_2") (pintype "unspecified"))
      (node (ref "U3") (pin "1") (pinfunction "1_1") (pintype "unspecified"))
      (node (ref "U4") (pin "3") (pinfunction "1IN+_3") (pintype "unspecified"))
    )
    (net (code "66") (name "Net-(U4-VCC+)") (class "Default")
      (node (ref "U4") (pin "8") (pinfunction "VCC+_8") (pintype "unspecified"))
      (node (ref "U5") (pin "5") (pinfunction "VOUT_5") (pintype "unspecified"))
      (node (ref "U9") (pin "2") (pinfunction "2_2") (pintype "unspecified"))
    )
    (net (code "67") (name "Net-(U5-BYPASS)") (class "Default")
      (node (ref "C16") (pin "2") (pinfunction "2_2") (pintype "input"))
      (node (ref "U5") (pin "4") (pinfunction "BYPASS_4") (pintype "unspecified"))
    )
    (net (code "68") (name "Net-(U12-3V3OUT)") (class "Default")
      (node (ref "C23") (pin "1") (pinfunction "1_1") (pintype "input"))
      (node (ref "U12") (pin "16") (pinfunction "3V3OUT_16") (pintype "unspecified"))
    )
    (net (code "69") (name "Net-(U12-AGND)") (class "Default")
      (node (ref "C18") (pin "1") (pinfunction "1_1") (pintype "input"))
      (node (ref "U12") (pin "24") (pinfunction "AGND_24") (pintype "unspecified"))
    )
    (net (code "70") (name "Net-(U12-CBUS0)") (class "Default")
      (node (ref "R5") (pin "2") (pinfunction "2_2") (pintype "unspecified"))
      (node (ref "U12") (pin "22") (pinfunction "CBUS0_22") (pintype "unspecified"))
    )
    (net (code "71") (name "Net-(U12-CBUS1)") (class "Default")
      (node (ref "R4") (pin "1") (pinfunction "1_1") (pintype "unspecified"))
      (node (ref "U12") (pin "21") (pinfunction "CBUS1_21") (pintype "unspecified"))
    )
    (net (code "72") (name "Net-(U12-VCC)") (class "Default")
      (node (ref "C20") (pin "1") (pinfunction "1_1") (pintype "input"))
      (node (ref "U12") (pin "19") (pinfunction "VCC_19") (pintype "unspecified"))
    )
    (net (code "73") (name "Net-(U12-VCCIO)") (class "Default")
      (node (ref "C22") (pin "1") (pinfunction "1_1") (pintype "input"))
      (node (ref "U12") (pin "1") (pinfunction "VCCIO_1") (pintype "unspecified"))
    )
    (net (code "74") (name "Net-(U14-1Y)") (class "Default")
      (node (ref "H1") (pin "3") (pinfunction "3_3") (pintype "unspecified"))
      (node (ref "U14") (pin "2") (pinfunction "1Y_2") (pintype "unspecified"))
    )
    (net (code "75") (name "VCC") (class "Default")
      (node (ref "R1") (pin "1") (pinfunction "1_1") (pintype "unspecified"))
    )
    (net (code "76") (name "unconnected-(H1-Pad11)") (class "Default")
      (node (ref "H1") (pin "11") (pinfunction "11_11") (pintype "unspecified"))
    )
    (net (code "77") (name "unconnected-(H1-Pad17)") (class "Default")
      (node (ref "H1") (pin "17") (pinfunction "17_17") (pintype "unspecified"))
    )
    (net (code "78") (name "unconnected-(H1-Pad19)") (class "Default")
      (node (ref "H1") (pin "19") (pinfunction "19_19") (pintype "unspecified"))
    )
    (net (code "79") (name "unconnected-(U4-2IN+-Pad5)") (class "Default")
      (node (ref "U4") (pin "5") (pinfunction "2IN+_5") (pintype "unspecified"))
    )
    (net (code "80") (name "unconnected-(U4-2IN{slash}--Pad6)") (class "Default")
      (node (ref "U4") (pin "6") (pinfunction "2IN/-_6") (pintype "unspecified"))
    )
    (net (code "81") (name "unconnected-(U4-2OUT-Pad7)") (class "Default")
      (node (ref "U4") (pin "7") (pinfunction "2OUT_7") (pintype "unspecified"))
    )
    (net (code "82") (name "unconnected-(U12-CBUS2-Pad10)") (class "Default")
      (node (ref "U12") (pin "10") (pinfunction "CBUS2_10") (pintype "unspecified"))
    )
    (net (code "83") (name "unconnected-(U12-CBUS3-Pad11)") (class "Default")
      (node (ref "U12") (pin "11") (pinfunction "CBUS3_11") (pintype "unspecified"))
    )
    (net (code "84") (name "unconnected-(U12-CBUS4-Pad9)") (class "Default")
      (node (ref "U12") (pin "9") (pinfunction "CBUS4_9") (pintype "unspecified"))
    )
    (net (code "85") (name "unconnected-(U12-DCD#-Pad7)") (class "Default")
      (node (ref "U12") (pin "7") (pinfunction "DCD#_7") (pintype "unspecified"))
    )
    (net (code "86") (name "unconnected-(U12-DSR#-Pad6)") (class "Default")
      (node (ref "U12") (pin "6") (pinfunction "DSR#_6") (pintype "unspecified"))
    )
    (net (code "87") (name "unconnected-(U12-DTR#-Pad31)") (class "Default")
      (node (ref "U12") (pin "31") (pinfunction "DTR#_31") (pintype "unspecified"))
    )
    (net (code "88") (name "unconnected-(U12-EP-Pad33)") (class "Default")
      (node (ref "U12") (pin "33") (pinfunction "EP_33") (pintype "unspecified"))
    )
    (net (code "89") (name "unconnected-(U12-NC-Pad5)") (class "Default")
      (node (ref "U12") (pin "5") (pinfunction "NC_5") (pintype "unspecified"))
    )
    (net (code "90") (name "unconnected-(U12-NC-Pad12)") (class "Default")
      (node (ref "U12") (pin "12") (pinfunction "NC_12") (pintype "unspecified"))
    )
    (net (code "91") (name "unconnected-(U12-NC-Pad13)") (class "Default")
      (node (ref "U12") (pin "13") (pinfunction "NC_13") (pintype "unspecified"))
    )
    (net (code "92") (name "unconnected-(U12-NC-Pad23)") (class "Default")
      (node (ref "U12") (pin "23") (pinfunction "NC_23") (pintype "unspecified"))
    )
    (net (code "93") (name "unconnected-(U12-NC-Pad25)") (class "Default")
      (node (ref "U12") (pin "25") (pinfunction "NC_25") (pintype "unspecified"))
    )
    (net (code "94") (name "unconnected-(U12-NC-Pad29)") (class "Default")
      (node (ref "U12") (pin "29") (pinfunction "NC_29") (pintype "unspecified"))
    )
    (net (code "95") (name "unconnected-(U12-OSCI-Pad27)") (class "Default")
      (node (ref "U12") (pin "27") (pinfunction "OSCI_27") (pintype "unspecified"))
    )
    (net (code "96") (name "unconnected-(U12-OSCO-Pad28)") (class "Default")
      (node (ref "U12") (pin "28") (pinfunction "OSCO_28") (pintype "unspecified"))
    )
    (net (code "97") (name "unconnected-(U12-RI#-Pad3)") (class "Default")
      (node (ref "U12") (pin "3") (pinfunction "RI#_3") (pintype "unspecified"))
    )
    (net (code "98") (name "unconnected-(U14-2A-Pad3)") (class "Default")
      (node (ref "U14") (pin "3") (pinfunction "2A_3") (pintype "unspecified"))
    )
    (net (code "99") (name "unconnected-(U14-2Y-Pad4)") (class "Default")
      (node (ref "U14") (pin "4") (pinfunction "2Y_4") (pintype "unspecified"))
    )
    (net (code "100") (name "unconnected-(U14-3A-Pad5)") (class "Default")
      (node (ref "U14") (pin "5") (pinfunction "3A_5") (pintype "unspecified"))
    )
    (net (code "101") (name "unconnected-(U14-3Y-Pad6)") (class "Default")
      (node (ref "U14") (pin "6") (pinfunction "3Y_6") (pintype "unspecified"))
    )
    (net (code "102") (name "unconnected-(U14-4A-Pad9)") (class "Default")
      (node (ref "U14") (pin "9") (pinfunction "4A_9") (pintype "unspecified"))
    )
    (net (code "103") (name "unconnected-(U14-4Y-Pad8)") (class "Default")
      (node (ref "U14") (pin "8") (pinfunction "4Y_8") (pintype "unspecified"))
    )
    (net (code "104") (name "unconnected-(U14-5A-Pad11)") (class "Default")
      (node (ref "U14") (pin "11") (pinfunction "5A_11") (pintype "unspecified"))
    )
    (net (code "105") (name "unconnected-(U14-5Y-Pad10)") (class "Default")
      (node (ref "U14") (pin "10") (pinfunction "5Y_10") (pintype "unspecified"))
    )
    (net (code "106") (name "unconnected-(U14-6A-Pad13)") (class "Default")
      (node (ref "U14") (pin "13") (pinfunction "6A_13") (pintype "unspecified"))
    )
    (net (code "107") (name "unconnected-(U14-6Y-Pad12)") (class "Default")
      (node (ref "U14") (pin "12") (pinfunction "6Y_12") (pintype "unspecified"))
    )
  )
)
